# BrewPi_LCD_Shield.net
KiCad netlist of a schematic drawn in EAGLE
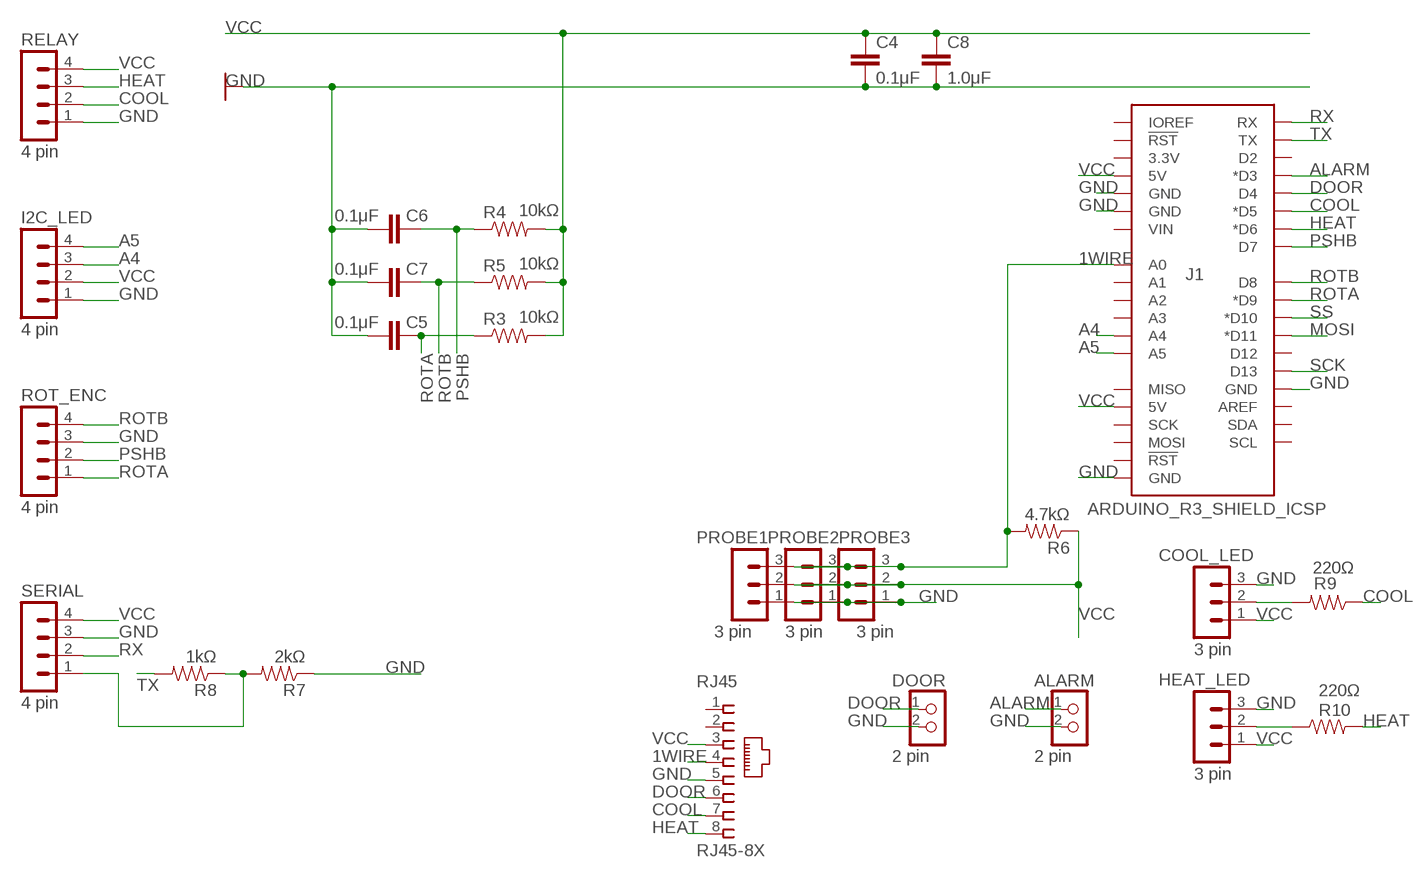
[diagram p0: schematic, sheet 1]

(export (version "E")
  (design (tool "Eeschema 10.0.6"))
  (components
    (comp (ref "ALARM")
      (value "2 pin")
      (footprint "eagle-import:HEADER02-1")
      (libsource (lib "eagle-import") (part "HEADER02-1"))
    )
    (comp (ref "C4")
      (value "0.1μF")
      (footprint "eagle-import:CAP-PTH-SMALL-KIT")
      (libsource (lib "eagle-import") (part "CAPKIT"))
    )
    (comp (ref "C5")
      (value "0.1μF")
      (footprint "eagle-import:CAP-PTH-SMALL-KIT")
      (libsource (lib "eagle-import") (part "CAPKIT"))
    )
    (comp (ref "C6")
      (value "0.1μF")
      (footprint "eagle-import:CAP-PTH-SMALL-KIT")
      (libsource (lib "eagle-import") (part "CAPKIT"))
    )
    (comp (ref "C7")
      (value "0.1μF")
      (footprint "eagle-import:CAP-PTH-SMALL-KIT")
      (libsource (lib "eagle-import") (part "CAPKIT"))
    )
    (comp (ref "C8")
      (value "1.0μF")
      (footprint "eagle-import:CAP-PTH-SMALL-KIT")
      (libsource (lib "eagle-import") (part "CAPKIT"))
    )
    (comp (ref "COOL_LED")
      (value "3 pin")
      (footprint "eagle-import:HEADER03-1")
      (libsource (lib "eagle-import") (part "HEADER03-1"))
    )
    (comp (ref "DOOR")
      (value "2 pin")
      (footprint "eagle-import:HEADER02-1")
      (libsource (lib "eagle-import") (part "HEADER02-1"))
    )
    (comp (ref "HEAT_LED")
      (value "3 pin")
      (footprint "eagle-import:HEADER03-1")
      (libsource (lib "eagle-import") (part "HEADER03-1"))
    )
    (comp (ref "I2C_LED")
      (value "4 pin")
      (footprint "eagle-import:HEADER04-1")
      (libsource (lib "eagle-import") (part "HEADER04-1"))
    )
    (comp (ref "J1")
      (value "ARDUINO_R3_SHIELD_ICSP")
      (footprint "eagle-import:UNO_R3_SHIELD_ICSP")
      (libsource (lib "eagle-import") (part "ARDUINO_R3_SHIELD_ICSP"))
    )
    (comp (ref "PROBE1")
      (value "3 pin")
      (footprint "eagle-import:HEADER03-1")
      (libsource (lib "eagle-import") (part "HEADER03-1"))
    )
    (comp (ref "PROBE2")
      (value "3 pin")
      (footprint "eagle-import:HEADER03-1")
      (libsource (lib "eagle-import") (part "HEADER03-1"))
    )
    (comp (ref "PROBE3")
      (value "3 pin")
      (footprint "eagle-import:HEADER03-1")
      (libsource (lib "eagle-import") (part "HEADER03-1"))
    )
    (comp (ref "R3")
      (value "10kΩ")
      (footprint "eagle-import:AXIAL-0.3")
      (libsource (lib "eagle-import") (part "RESISTORAXIAL-0.3"))
    )
    (comp (ref "R4")
      (value "10kΩ")
      (footprint "eagle-import:AXIAL-0.3")
      (libsource (lib "eagle-import") (part "RESISTORAXIAL-0.3"))
    )
    (comp (ref "R5")
      (value "10kΩ")
      (footprint "eagle-import:AXIAL-0.3")
      (libsource (lib "eagle-import") (part "RESISTORAXIAL-0.3"))
    )
    (comp (ref "R6")
      (value "4.7kΩ")
      (footprint "eagle-import:AXIAL-0.3")
      (libsource (lib "eagle-import") (part "RESISTORAXIAL-0.3"))
    )
    (comp (ref "R7")
      (value "2kΩ")
      (footprint "eagle-import:AXIAL-0.3")
      (libsource (lib "eagle-import") (part "RESISTORAXIAL-0.3"))
    )
    (comp (ref "R8")
      (value "1kΩ")
      (footprint "eagle-import:AXIAL-0.3")
      (libsource (lib "eagle-import") (part "RESISTORAXIAL-0.3"))
    )
    (comp (ref "R9")
      (value "220Ω")
      (footprint "eagle-import:AXIAL-0.3")
      (libsource (lib "eagle-import") (part "RESISTORAXIAL-0.3"))
    )
    (comp (ref "R10")
      (value "220Ω")
      (footprint "eagle-import:AXIAL-0.3")
      (libsource (lib "eagle-import") (part "RESISTORAXIAL-0.3"))
    )
    (comp (ref "RELAY")
      (value "4 pin")
      (footprint "eagle-import:HEADER04-1")
      (libsource (lib "eagle-import") (part "HEADER04-1"))
    )
    (comp (ref "RJ45")
      (value "RJ45-8X")
      (footprint "eagle-import:RJ45-NO-SHIELD")
      (libsource (lib "eagle-import") (part "RJ45-8X"))
    )
    (comp (ref "ROT_ENC")
      (value "4 pin")
      (footprint "eagle-import:HEADER04-1")
      (libsource (lib "eagle-import") (part "HEADER04-1"))
    )
    (comp (ref "SERIAL")
      (value "4 pin")
      (footprint "eagle-import:HEADER04-1")
      (libsource (lib "eagle-import") (part "HEADER04-1"))
    )
  )
  (nets
    (net (code "1") (name "/1WIRE") (class "Default")
      (node (ref "J1") (pin "A0") (pinfunction "A0_A0") (pintype "bidirectional"))
      (node (ref "PROBE1") (pin "3") (pinfunction "3_3") (pintype "passive"))
      (node (ref "PROBE2") (pin "3") (pinfunction "3_3") (pintype "passive"))
      (node (ref "PROBE3") (pin "3") (pinfunction "3_3") (pintype "passive"))
      (node (ref "R6") (pin "P$2") (pinfunction "2_P$2") (pintype "passive"))
      (node (ref "RJ45") (pin "4") (pinfunction "4_4") (pintype "passive"))
    )
    (net (code "2") (name "/A4") (class "Default")
      (node (ref "I2C_LED") (pin "3") (pinfunction "3_3") (pintype "passive"))
      (node (ref "J1") (pin "A4") (pinfunction "A4_A4") (pintype "bidirectional"))
    )
    (net (code "3") (name "/A5") (class "Default")
      (node (ref "I2C_LED") (pin "4") (pinfunction "4_4") (pintype "passive"))
      (node (ref "J1") (pin "A5") (pinfunction "A5_A5") (pintype "bidirectional"))
    )
    (net (code "4") (name "/ALARM") (class "Default")
      (node (ref "ALARM") (pin "1") (pinfunction "1_1") (pintype "passive"))
      (node (ref "J1") (pin "D3") (pinfunction "*D3_D3") (pintype "bidirectional"))
    )
    (net (code "5") (name "/COOL") (class "Default")
      (node (ref "J1") (pin "D5") (pinfunction "*D5_D5") (pintype "bidirectional"))
      (node (ref "R9") (pin "P$1") (pinfunction "1_P$1") (pintype "passive"))
      (node (ref "RELAY") (pin "2") (pinfunction "2_2") (pintype "passive"))
      (node (ref "RJ45") (pin "7") (pinfunction "7_7") (pintype "passive"))
    )
    (net (code "6") (name "/DOOR") (class "Default")
      (node (ref "DOOR") (pin "1") (pinfunction "1_1") (pintype "passive"))
      (node (ref "J1") (pin "D4") (pinfunction "D4_D4") (pintype "bidirectional"))
      (node (ref "RJ45") (pin "6") (pinfunction "6_6") (pintype "passive"))
    )
    (net (code "7") (name "/HEAT") (class "Default")
      (node (ref "J1") (pin "D6") (pinfunction "*D6_D6") (pintype "bidirectional"))
      (node (ref "R10") (pin "P$2") (pinfunction "2_P$2") (pintype "passive"))
      (node (ref "RELAY") (pin "3") (pinfunction "3_3") (pintype "passive"))
      (node (ref "RJ45") (pin "8") (pinfunction "8_8") (pintype "passive"))
    )
    (net (code "8") (name "/MOSI") (class "Default")
      (node (ref "J1") (pin "D11") (pinfunction "*D11_D11") (pintype "bidirectional"))
    )
    (net (code "9") (name "/PSHB") (class "Default")
      (node (ref "C6") (pin "1") (pinfunction "1_1") (pintype "passive"))
      (node (ref "J1") (pin "D7") (pinfunction "D7_D7") (pintype "bidirectional"))
      (node (ref "R4") (pin "P$1") (pinfunction "1_P$1") (pintype "passive"))
      (node (ref "ROT_ENC") (pin "2") (pinfunction "2_2") (pintype "passive"))
    )
    (net (code "10") (name "/ROTA") (class "Default")
      (node (ref "C5") (pin "1") (pinfunction "1_1") (pintype "passive"))
      (node (ref "J1") (pin "D9") (pinfunction "*D9_D9") (pintype "bidirectional"))
      (node (ref "R3") (pin "P$1") (pinfunction "1_P$1") (pintype "passive"))
      (node (ref "ROT_ENC") (pin "1") (pinfunction "1_1") (pintype "passive"))
    )
    (net (code "11") (name "/ROTB") (class "Default")
      (node (ref "C7") (pin "1") (pinfunction "1_1") (pintype "passive"))
      (node (ref "J1") (pin "D8") (pinfunction "D8_D8") (pintype "bidirectional"))
      (node (ref "R5") (pin "P$1") (pinfunction "1_P$1") (pintype "passive"))
      (node (ref "ROT_ENC") (pin "4") (pinfunction "4_4") (pintype "passive"))
    )
    (net (code "12") (name "/RX") (class "Default")
      (node (ref "J1") (pin "RX") (pinfunction "RX_RX") (pintype "bidirectional"))
      (node (ref "SERIAL") (pin "2") (pinfunction "2_2") (pintype "passive"))
    )
    (net (code "13") (name "/SCK") (class "Default")
      (node (ref "J1") (pin "D13") (pinfunction "D13_D13") (pintype "bidirectional"))
    )
    (net (code "14") (name "/SS") (class "Default")
      (node (ref "J1") (pin "D10") (pinfunction "*D10_D10") (pintype "bidirectional"))
    )
    (net (code "15") (name "/TX") (class "Default")
      (node (ref "J1") (pin "TX") (pinfunction "TX_TX") (pintype "bidirectional"))
      (node (ref "R8") (pin "P$2") (pinfunction "2_P$2") (pintype "passive"))
    )
    (net (code "16") (name "/VCC") (class "Default")
      (node (ref "C4") (pin "1") (pinfunction "1_1") (pintype "passive"))
      (node (ref "C8") (pin "1") (pinfunction "1_1") (pintype "passive"))
      (node (ref "COOL_LED") (pin "1") (pinfunction "1_1") (pintype "passive"))
      (node (ref "HEAT_LED") (pin "1") (pinfunction "1_1") (pintype "passive"))
      (node (ref "I2C_LED") (pin "2") (pinfunction "2_2") (pintype "passive"))
      (node (ref "J1") (pin "5V") (pinfunction "5V_5V") (pintype "bidirectional"))
      (node (ref "J1") (pin "5V_ICSP") (pinfunction "5V_5V_ICSP") (pintype "bidirectional"))
      (node (ref "PROBE1") (pin "2") (pinfunction "2_2") (pintype "passive"))
      (node (ref "PROBE2") (pin "2") (pinfunction "2_2") (pintype "passive"))
      (node (ref "PROBE3") (pin "2") (pinfunction "2_2") (pintype "passive"))
      (node (ref "R3") (pin "P$2") (pinfunction "2_P$2") (pintype "passive"))
      (node (ref "R4") (pin "P$2") (pinfunction "2_P$2") (pintype "passive"))
      (node (ref "R5") (pin "P$2") (pinfunction "2_P$2") (pintype "passive"))
      (node (ref "R6") (pin "P$1") (pinfunction "1_P$1") (pintype "passive"))
      (node (ref "RELAY") (pin "4") (pinfunction "4_4") (pintype "passive"))
      (node (ref "RJ45") (pin "3") (pinfunction "3_3") (pintype "passive"))
      (node (ref "SERIAL") (pin "4") (pinfunction "4_4") (pintype "passive"))
    )
    (net (code "17") (name "GND") (class "Default")
      (node (ref "ALARM") (pin "2") (pinfunction "2_2") (pintype "passive"))
      (node (ref "C4") (pin "2") (pinfunction "2_2") (pintype "passive"))
      (node (ref "C5") (pin "2") (pinfunction "2_2") (pintype "passive"))
      (node (ref "C6") (pin "2") (pinfunction "2_2") (pintype "passive"))
      (node (ref "C7") (pin "2") (pinfunction "2_2") (pintype "passive"))
      (node (ref "C8") (pin "2") (pinfunction "2_2") (pintype "passive"))
      (node (ref "COOL_LED") (pin "3") (pinfunction "3_3") (pintype "passive"))
      (node (ref "DOOR") (pin "2") (pinfunction "2_2") (pintype "passive"))
      (node (ref "HEAT_LED") (pin "3") (pinfunction "3_3") (pintype "passive"))
      (node (ref "I2C_LED") (pin "1") (pinfunction "1_1") (pintype "passive"))
      (node (ref "J1") (pin "GND@0") (pinfunction "GND_GND@0") (pintype "bidirectional"))
      (node (ref "J1") (pin "GND@1") (pinfunction "GND_GND@1") (pintype "bidirectional"))
      (node (ref "J1") (pin "GND@2") (pinfunction "GND_GND@2") (pintype "bidirectional"))
      (node (ref "J1") (pin "GND_ICSP") (pinfunction "GND_GND_ICSP") (pintype "bidirectional"))
      (node (ref "PROBE1") (pin "1") (pinfunction "1_1") (pintype "passive"))
      (node (ref "PROBE2") (pin "1") (pinfunction "1_1") (pintype "passive"))
      (node (ref "PROBE3") (pin "1") (pinfunction "1_1") (pintype "passive"))
      (node (ref "R7") (pin "P$1") (pinfunction "1_P$1") (pintype "passive"))
      (node (ref "RELAY") (pin "1") (pinfunction "1_1") (pintype "passive"))
      (node (ref "RJ45") (pin "5") (pinfunction "5_5") (pintype "passive"))
      (node (ref "ROT_ENC") (pin "3") (pinfunction "3_3") (pintype "passive"))
      (node (ref "SERIAL") (pin "3") (pinfunction "3_3") (pintype "passive"))
    )
    (net (code "18") (name "Net-(R7-2)") (class "Default")
      (node (ref "R7") (pin "P$2") (pinfunction "2_P$2") (pintype "passive"))
      (node (ref "R8") (pin "P$1") (pinfunction "1_P$1") (pintype "passive"))
      (node (ref "SERIAL") (pin "1") (pinfunction "1_1") (pintype "passive"))
    )
    (net (code "19") (name "Net-(R9-2)") (class "Default")
      (node (ref "COOL_LED") (pin "2") (pinfunction "2_2") (pintype "passive"))
      (node (ref "R9") (pin "P$2") (pinfunction "2_P$2") (pintype "passive"))
    )
    (net (code "20") (name "Net-(R10-1)") (class "Default")
      (node (ref "HEAT_LED") (pin "2") (pinfunction "2_2") (pintype "passive"))
      (node (ref "R10") (pin "P$1") (pinfunction "1_P$1") (pintype "passive"))
    )
    (net (code "21") (name "unconnected-(J1-Pad3.3V)") (class "Default")
      (node (ref "J1") (pin "3.3V") (pinfunction "3.3V_3.3V") (pintype "bidirectional"))
    )
    (net (code "22") (name "unconnected-(J1-PadA1)") (class "Default")
      (node (ref "J1") (pin "A1") (pinfunction "A1_A1") (pintype "bidirectional"))
    )
    (net (code "23") (name "unconnected-(J1-PadA2)") (class "Default")
      (node (ref "J1") (pin "A2") (pinfunction "A2_A2") (pintype "bidirectional"))
    )
    (net (code "24") (name "unconnected-(J1-PadA3)") (class "Default")
      (node (ref "J1") (pin "A3") (pinfunction "A3_A3") (pintype "bidirectional"))
    )
    (net (code "25") (name "unconnected-(J1-PadAREF)") (class "Default")
      (node (ref "J1") (pin "AREF") (pinfunction "AREF_AREF") (pintype "bidirectional"))
    )
    (net (code "26") (name "unconnected-(J1-PadD2)") (class "Default")
      (node (ref "J1") (pin "D2") (pinfunction "D2_D2") (pintype "bidirectional"))
    )
    (net (code "27") (name "unconnected-(J1-PadD12)") (class "Default")
      (node (ref "J1") (pin "D12") (pinfunction "D12_D12") (pintype "bidirectional"))
    )
    (net (code "28") (name "unconnected-(J1-PadIOREF)") (class "Default")
      (node (ref "J1") (pin "IOREF") (pinfunction "IOREF_IOREF") (pintype "bidirectional"))
    )
    (net (code "29") (name "unconnected-(J1-PadMISO)") (class "Default")
      (node (ref "J1") (pin "MISO") (pinfunction "MISO_MISO") (pintype "bidirectional"))
    )
    (net (code "30") (name "unconnected-(J1-PadMOSI)") (class "Default")
      (node (ref "J1") (pin "MOSI") (pinfunction "MOSI_MOSI") (pintype "bidirectional"))
    )
    (net (code "31") (name "unconnected-(J1-PadSCK)") (class "Default")
      (node (ref "J1") (pin "SCK") (pinfunction "SCK_SCK") (pintype "bidirectional"))
    )
    (net (code "32") (name "unconnected-(J1-PadSCL)") (class "Default")
      (node (ref "J1") (pin "SCL") (pinfunction "SCL_SCL") (pintype "bidirectional"))
    )
    (net (code "33") (name "unconnected-(J1-PadSDA)") (class "Default")
      (node (ref "J1") (pin "SDA") (pinfunction "SDA_SDA") (pintype "bidirectional"))
    )
    (net (code "34") (name "unconnected-(J1-PadVIN)") (class "Default")
      (node (ref "J1") (pin "VIN") (pinfunction "VIN_VIN") (pintype "bidirectional"))
    )
    (net (code "35") (name "unconnected-(J1-~{RST}-PadRES)") (class "Default")
      (node (ref "J1") (pin "RES") (pinfunction "~{RST}_RES") (pintype "bidirectional"))
    )
    (net (code "36") (name "unconnected-(J1-~{RST}-PadRST_ICSP)") (class "Default")
      (node (ref "J1") (pin "RST_ICSP") (pinfunction "~{RST}_RST_ICSP") (pintype "bidirectional"))
    )
    (net (code "37") (name "unconnected-(RJ45-Pad1)") (class "Default")
      (node (ref "RJ45") (pin "1") (pinfunction "1_1") (pintype "passive"))
    )
    (net (code "38") (name "unconnected-(RJ45-Pad2)") (class "Default")
      (node (ref "RJ45") (pin "2") (pinfunction "2_2") (pintype "passive"))
    )
  )
)
